# Heart_Rate.net
KiCad netlist of a schematic drawn in Altium Designer
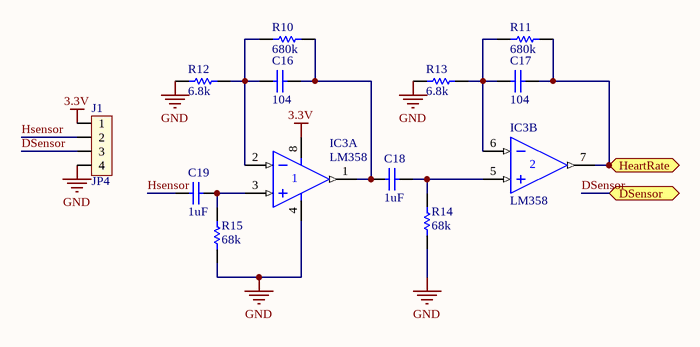
[diagram p0: Heart_Rate.SchDoc]

(export (version "E")
  (design (tool "Eeschema 10.0.6"))
  (components
    (comp (ref "C16")
      (value "104")
      (footprint "Cap 0805")
      (libsource (lib "HoangViet_AltiumLib") (part "Cap_0805"))
    )
    (comp (ref "C17")
      (value "104")
      (footprint "Cap 0805")
      (libsource (lib "HoangViet_AltiumLib") (part "Cap_0805"))
    )
    (comp (ref "C18")
      (value "1uF")
      (footprint "Cap 0805")
      (libsource (lib "HoangViet_AltiumLib") (part "Cap_0805"))
    )
    (comp (ref "C19")
      (value "1uF")
      (footprint "Cap 0805")
      (libsource (lib "HoangViet_AltiumLib") (part "Cap_0805"))
    )
    (comp (ref "IC3")
      (value "LM358")
      (footprint "SOP-8")
      (description "LM358_OPAMP")
      (libsource (lib "HoangViet_AltiumLib") (part "LM358_SMD"))
    )
    (comp (ref "J1") (value "JP4") (footprint "JP_CAI_4") (libsource (lib "linhien69") (part "JP4")))
    (comp (ref "R10")
      (value "680k")
      (footprint "RES 0805")
      (description "resistor smd0805")
      (libsource (lib "HoangViet_AltiumLib") (part "Res_0805"))
    )
    (comp (ref "R11")
      (value "680k")
      (footprint "RES 0805")
      (description "resistor smd0805")
      (libsource (lib "HoangViet_AltiumLib") (part "Res_0805"))
    )
    (comp (ref "R12")
      (value "6.8k")
      (footprint "RES 0805")
      (description "resistor smd0805")
      (libsource (lib "HoangViet_AltiumLib") (part "Res_0805"))
    )
    (comp (ref "R13")
      (value "6.8k")
      (footprint "RES 0805")
      (description "resistor smd0805")
      (libsource (lib "HoangViet_AltiumLib") (part "Res_0805"))
    )
    (comp (ref "R14")
      (value "68k")
      (footprint "RES 0805")
      (description "resistor smd0805")
      (libsource (lib "HoangViet_AltiumLib") (part "Res_0805"))
    )
    (comp (ref "R15")
      (value "68k")
      (footprint "RES 0805")
      (description "resistor smd0805")
      (libsource (lib "HoangViet_AltiumLib") (part "Res_0805"))
    )
  )
  (nets
    (net (code "1") (name "/DSensor") (class "Default")
      (node (ref "J1") (pin "3") (pinfunction "3_3") (pintype "passive"))
    )
    (net (code "2") (name "/HeartRate") (class "Default")
      (node (ref "C17") (pin "1") (pinfunction "1_1") (pintype "passive"))
      (node (ref "IC3") (pin "7") (pinfunction "OUT_7") (pintype "output"))
      (node (ref "R11") (pin "1") (pinfunction "1_1") (pintype "passive"))
    )
    (net (code "3") (name "/Hsensor") (class "Default")
      (node (ref "C19") (pin "2") (pinfunction "2_2") (pintype "passive"))
      (node (ref "J1") (pin "2") (pinfunction "2_2") (pintype "passive"))
    )
    (net (code "4") (name "3.3V") (class "Default")
      (node (ref "IC3") (pin "8") (pinfunction "V+_8") (pintype "power_in"))
      (node (ref "J1") (pin "1") (pinfunction "1_1") (pintype "passive"))
    )
    (net (code "5") (name "GND") (class "Default")
      (node (ref "IC3") (pin "4") (pinfunction "V-_4") (pintype "power_in"))
      (node (ref "J1") (pin "4") (pinfunction "4_4") (pintype "passive"))
      (node (ref "R12") (pin "2") (pinfunction "2_2") (pintype "passive"))
      (node (ref "R13") (pin "2") (pinfunction "2_2") (pintype "passive"))
      (node (ref "R14") (pin "1") (pinfunction "1_1") (pintype "passive"))
      (node (ref "R15") (pin "1") (pinfunction "1_1") (pintype "passive"))
    )
    (net (code "6") (name "Net-(IC3A-IN+)") (class "Default")
      (node (ref "C19") (pin "1") (pinfunction "1_1") (pintype "passive"))
      (node (ref "IC3") (pin "3") (pinfunction "IN+_3") (pintype "input"))
      (node (ref "R15") (pin "2") (pinfunction "2_2") (pintype "passive"))
    )
    (net (code "7") (name "Net-(IC3A-IN-)") (class "Default")
      (node (ref "C16") (pin "2") (pinfunction "2_2") (pintype "passive"))
      (node (ref "IC3") (pin "2") (pinfunction "IN-_2") (pintype "input"))
      (node (ref "R10") (pin "2") (pinfunction "2_2") (pintype "passive"))
      (node (ref "R12") (pin "1") (pinfunction "1_1") (pintype "passive"))
    )
    (net (code "8") (name "Net-(IC3A-OUT)") (class "Default")
      (node (ref "C16") (pin "1") (pinfunction "1_1") (pintype "passive"))
      (node (ref "C18") (pin "2") (pinfunction "2_2") (pintype "passive"))
      (node (ref "IC3") (pin "1") (pinfunction "OUT_1") (pintype "output"))
      (node (ref "R10") (pin "1") (pinfunction "1_1") (pintype "passive"))
    )
    (net (code "9") (name "Net-(IC3B-IN+)") (class "Default")
      (node (ref "C18") (pin "1") (pinfunction "1_1") (pintype "passive"))
      (node (ref "IC3") (pin "5") (pinfunction "IN+_5") (pintype "input"))
      (node (ref "R14") (pin "2") (pinfunction "2_2") (pintype "passive"))
    )
    (net (code "10") (name "Net-(IC3B-IN-)") (class "Default")
      (node (ref "C17") (pin "2") (pinfunction "2_2") (pintype "passive"))
      (node (ref "IC3") (pin "6") (pinfunction "IN-_6") (pintype "input"))
      (node (ref "R11") (pin "2") (pinfunction "2_2") (pintype "passive"))
      (node (ref "R13") (pin "1") (pinfunction "1_1") (pintype "passive"))
    )
  )
)
